# STM32.net
KiCad netlist of a schematic drawn in Altium Designer
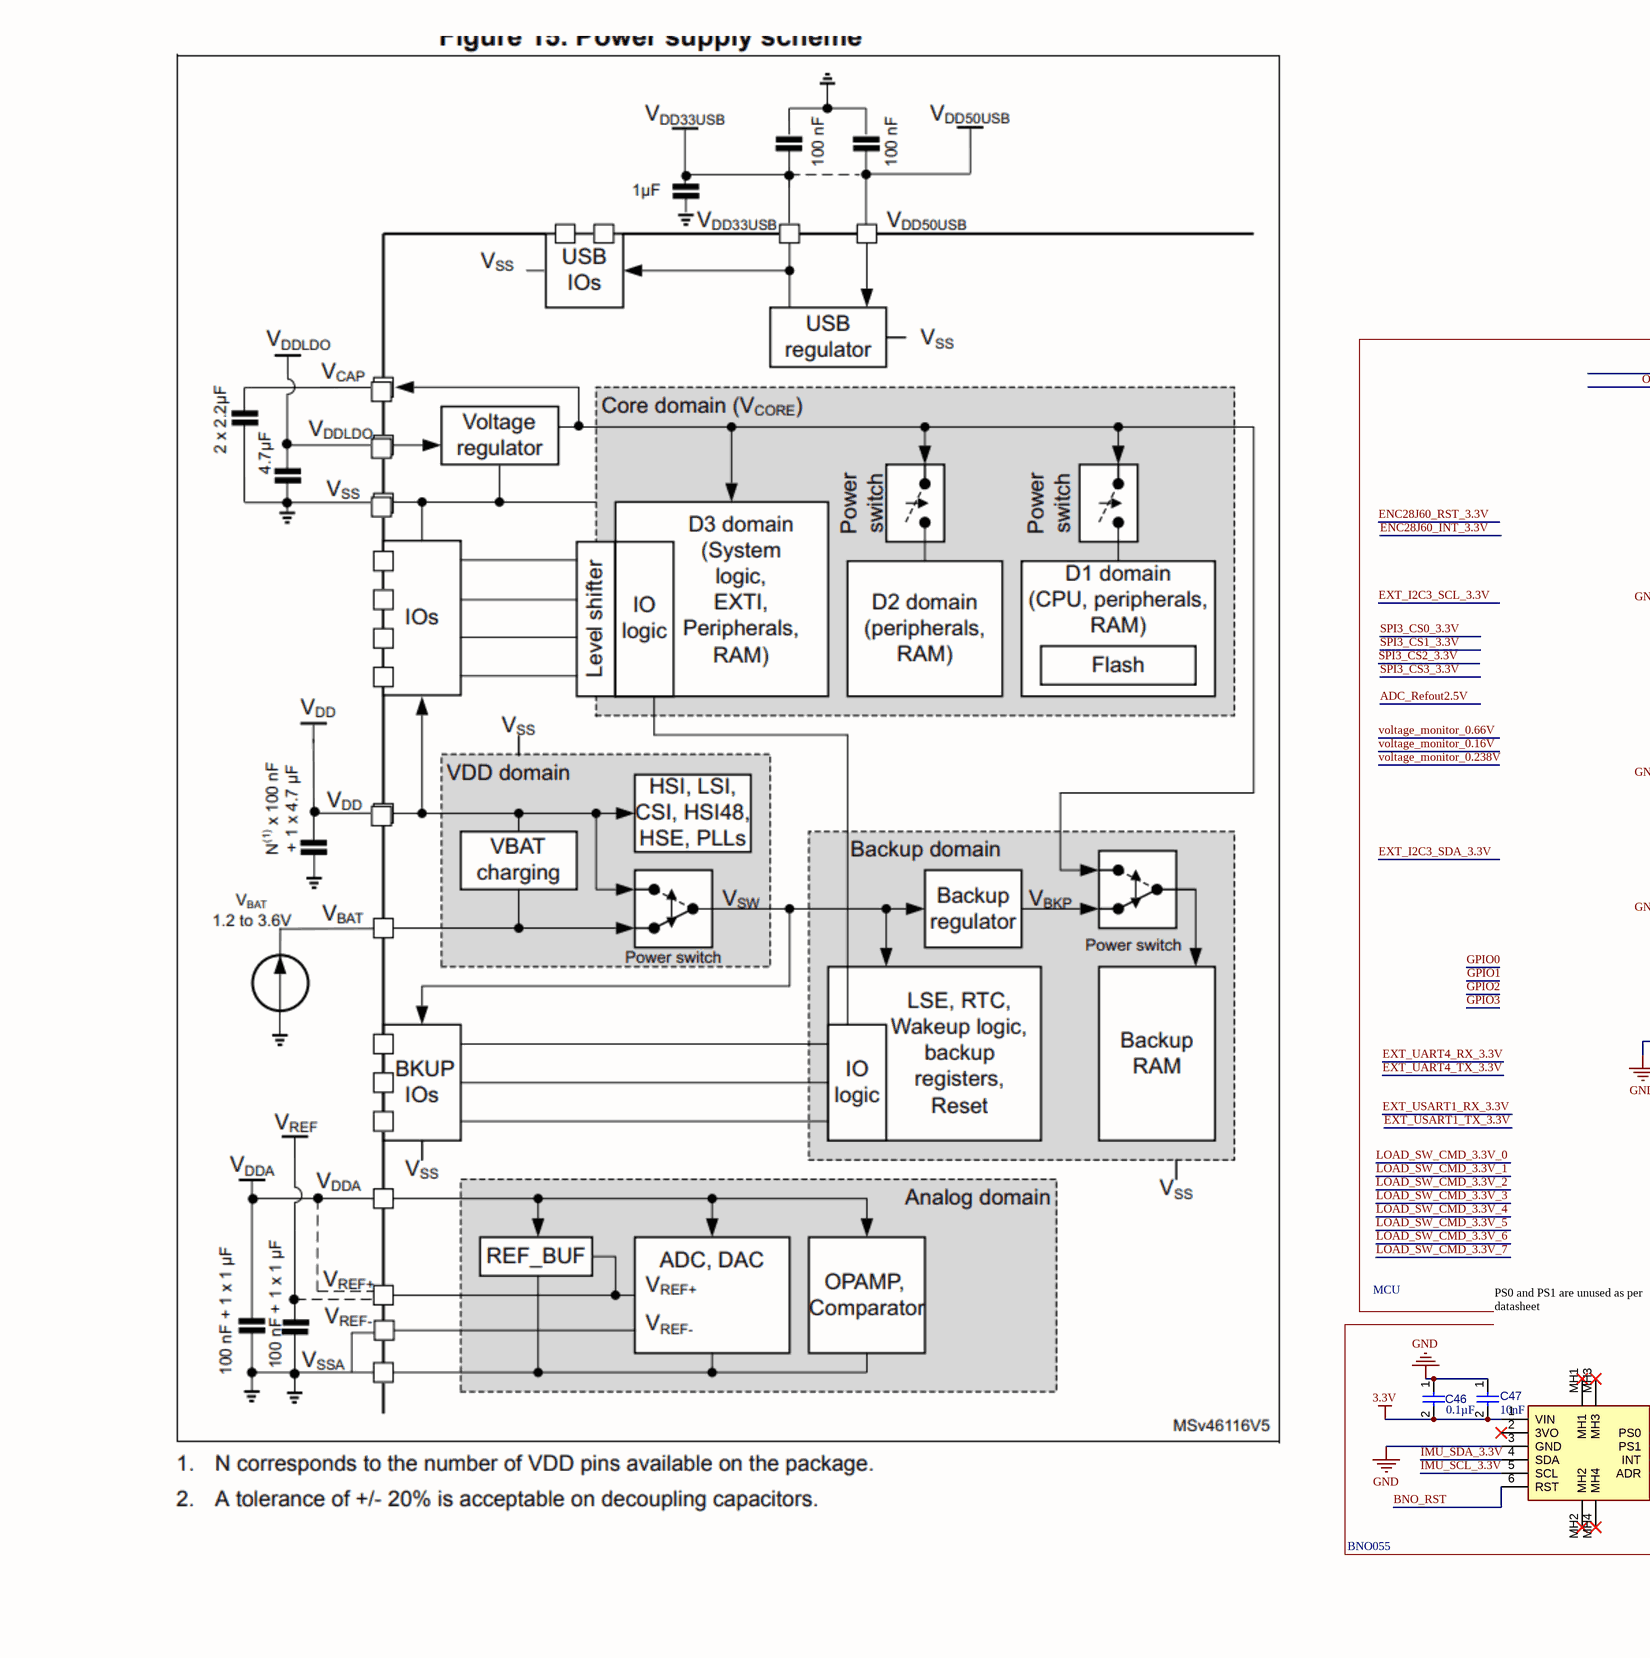
[diagram p0: STM32.SchDoc, left]
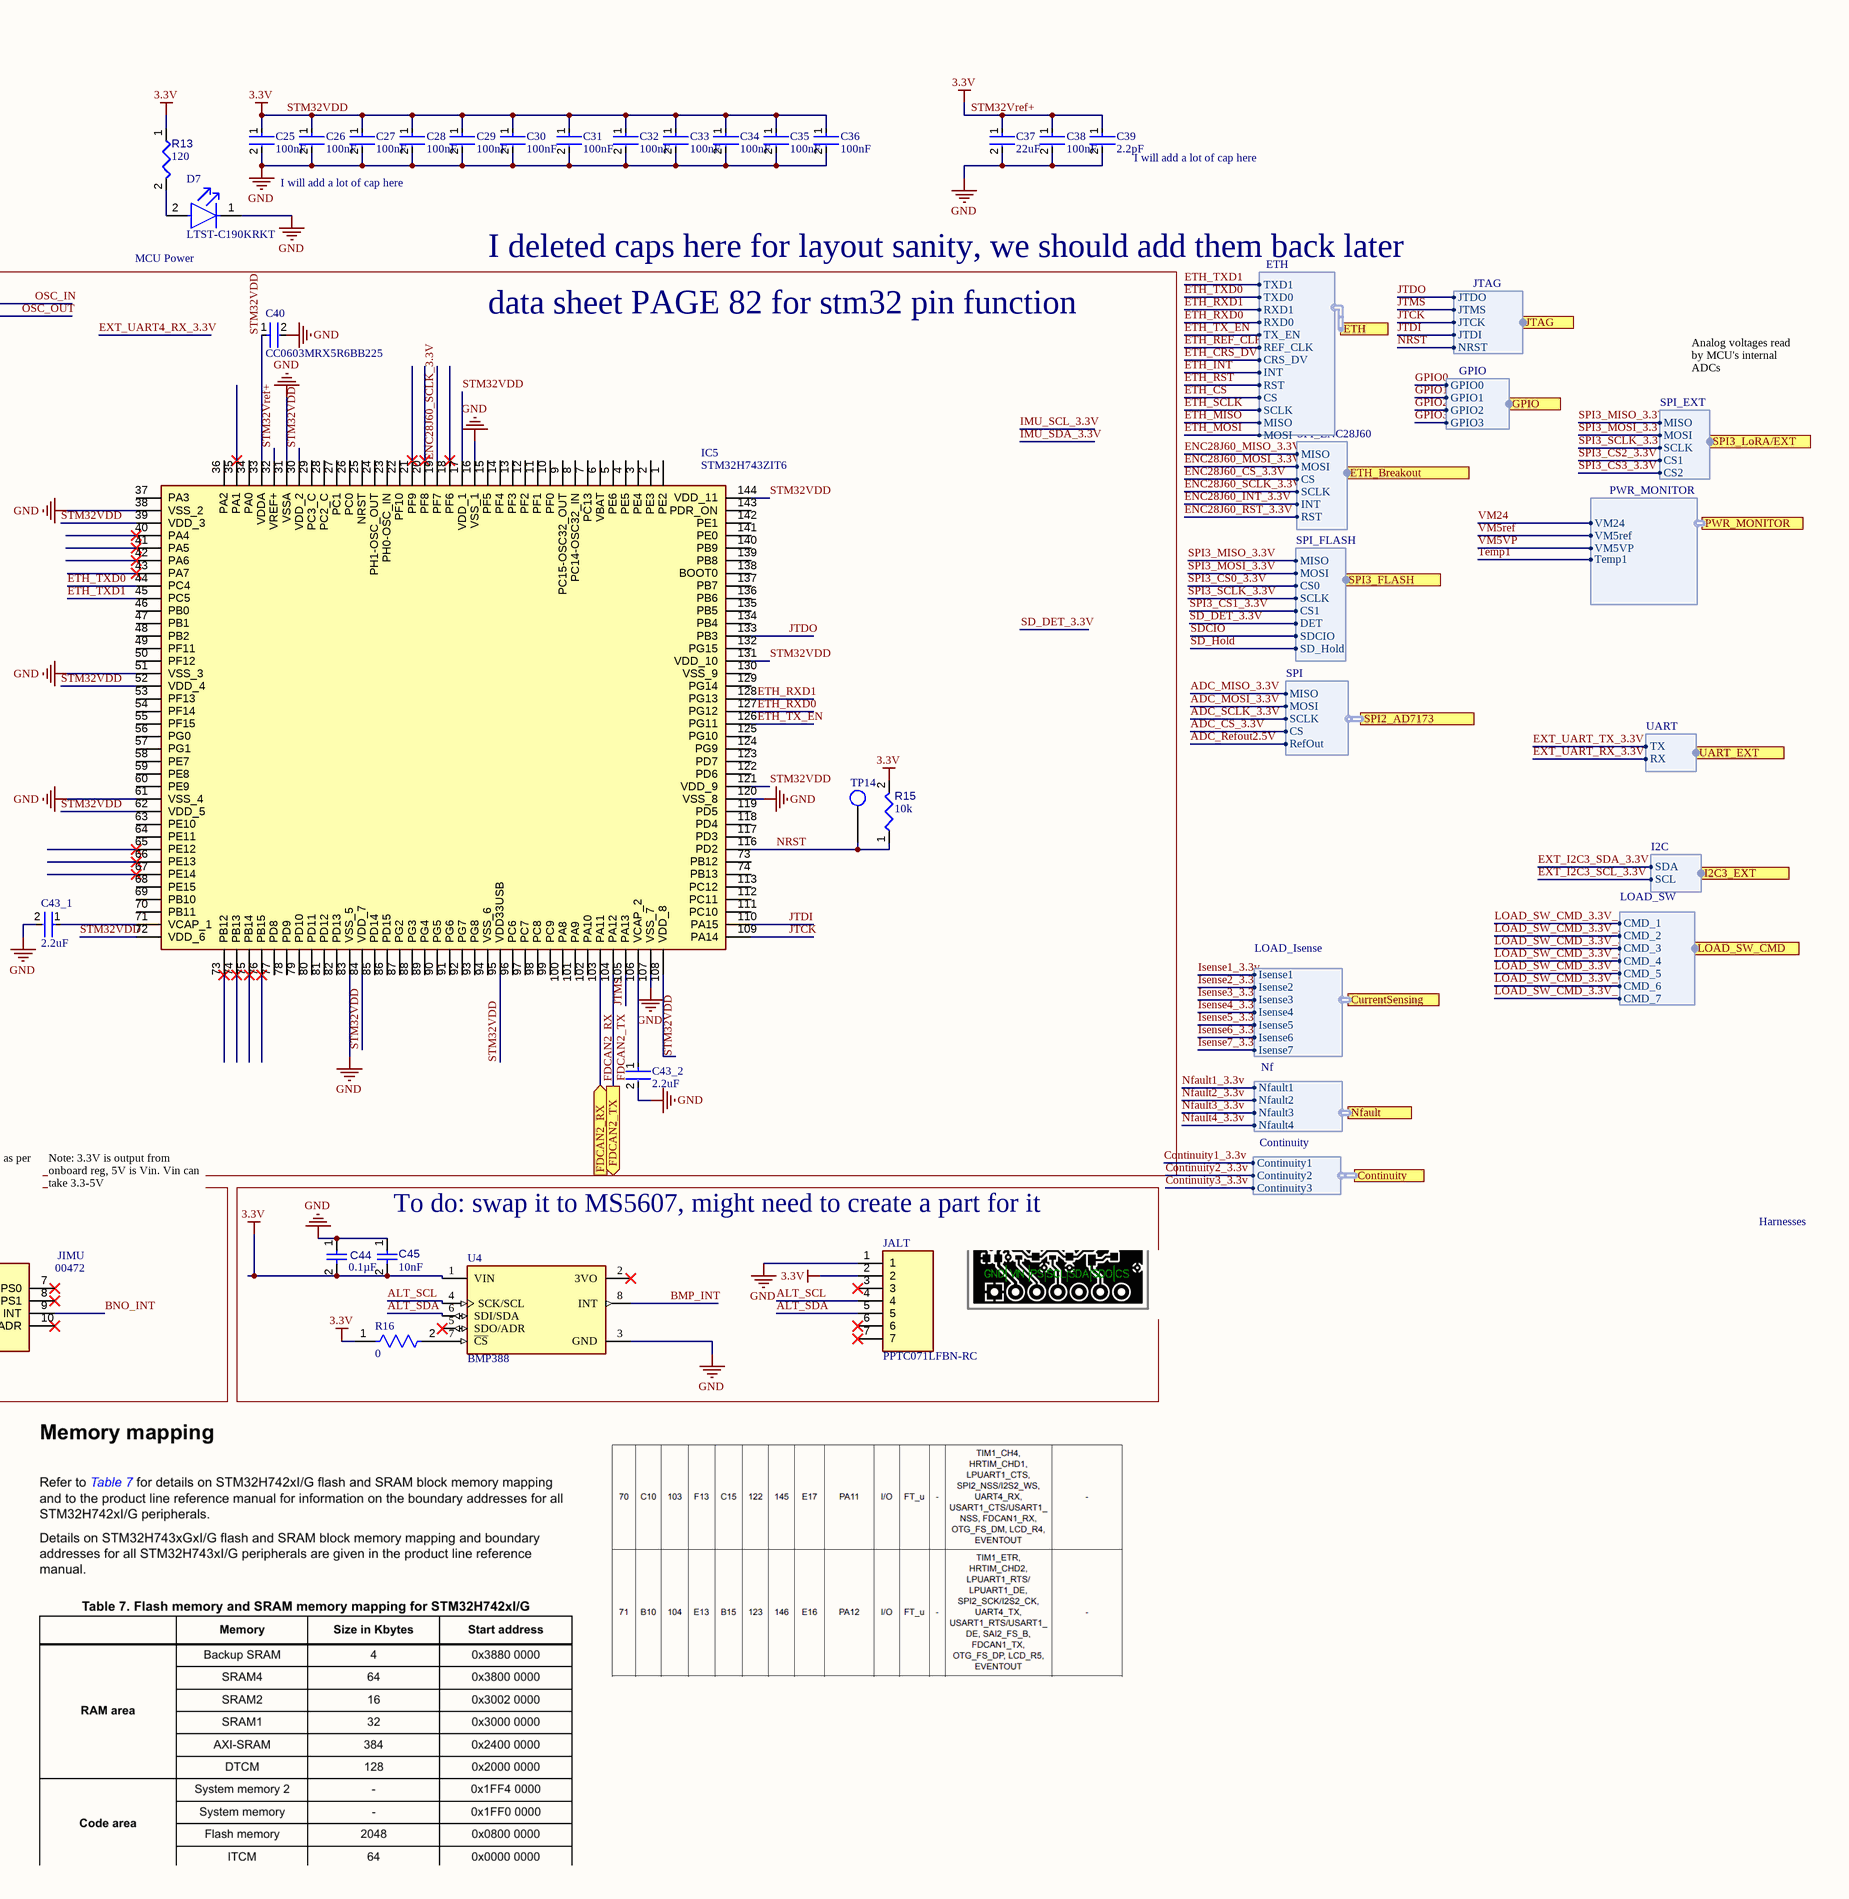
[diagram p1: STM32.SchDoc, right]

(export (version "E")
  (design (tool "Eeschema 10.0.6"))
  (components
    (comp (ref "C25")
      (value "100nF")
      (footprint "FP-CC0402-MFG")
      (description "CAP CER 0.1UF 16V X7R 0402")
      (fields (field (name "MANUFACTURER") "YAGEO") (field (name "TOLERANCE") "0.1"))
      (libsource (lib "Altium Content Vault") (part "11868f565c42a9108669ba33697ecf6"))
    )
    (comp (ref "C26")
      (value "100nF")
      (footprint "FP-CC0402-MFG")
      (description "CAP CER 0.1UF 16V X7R 0402")
      (fields (field (name "MANUFACTURER") "YAGEO") (field (name "TOLERANCE") "0.1"))
      (libsource (lib "Altium Content Vault") (part "11868f565c42a9108669ba33697ecf6"))
    )
    (comp (ref "C27")
      (value "100nF")
      (footprint "FP-CC0402-MFG")
      (description "CAP CER 0.1UF 16V X7R 0402")
      (fields (field (name "MANUFACTURER") "YAGEO") (field (name "TOLERANCE") "0.1"))
      (libsource (lib "Altium Content Vault") (part "11868f565c42a9108669ba33697ecf6"))
    )
    (comp (ref "C28")
      (value "100nF")
      (footprint "FP-CC0402-MFG")
      (description "CAP CER 0.1UF 16V X7R 0402")
      (fields (field (name "MANUFACTURER") "YAGEO") (field (name "TOLERANCE") "0.1"))
      (libsource (lib "Altium Content Vault") (part "11868f565c42a9108669ba33697ecf6"))
    )
    (comp (ref "C29")
      (value "100nF")
      (footprint "FP-CC0402-MFG")
      (description "CAP CER 0.1UF 16V X7R 0402")
      (fields (field (name "MANUFACTURER") "YAGEO") (field (name "TOLERANCE") "0.1"))
      (libsource (lib "Altium Content Vault") (part "11868f565c42a9108669ba33697ecf6"))
    )
    (comp (ref "C30")
      (value "100nF")
      (footprint "FP-CC0402-MFG")
      (description "CAP CER 0.1UF 16V X7R 0402")
      (fields (field (name "MANUFACTURER") "YAGEO") (field (name "TOLERANCE") "0.1"))
      (libsource (lib "Altium Content Vault") (part "11868f565c42a9108669ba33697ecf6"))
    )
    (comp (ref "C31")
      (value "100nF")
      (footprint "FP-CC0402-MFG")
      (description "CAP CER 0.1UF 16V X7R 0402")
      (fields (field (name "MANUFACTURER") "YAGEO") (field (name "TOLERANCE") "0.1"))
      (libsource (lib "Altium Content Vault") (part "11868f565c42a9108669ba33697ecf6"))
    )
    (comp (ref "C32")
      (value "100nF")
      (footprint "FP-CC0402-MFG")
      (description "CAP CER 0.1UF 16V X7R 0402")
      (fields (field (name "MANUFACTURER") "YAGEO") (field (name "TOLERANCE") "0.1"))
      (libsource (lib "Altium Content Vault") (part "11868f565c42a9108669ba33697ecf6"))
    )
    (comp (ref "C33")
      (value "100nF")
      (footprint "FP-CC0402-MFG")
      (description "CAP CER 0.1UF 16V X7R 0402")
      (fields (field (name "MANUFACTURER") "YAGEO") (field (name "TOLERANCE") "0.1"))
      (libsource (lib "Altium Content Vault") (part "11868f565c42a9108669ba33697ecf6"))
    )
    (comp (ref "C34")
      (value "100nF")
      (footprint "FP-CC0402-MFG")
      (description "CAP CER 0.1UF 16V X7R 0402")
      (fields (field (name "MANUFACTURER") "YAGEO") (field (name "TOLERANCE") "0.1"))
      (libsource (lib "Altium Content Vault") (part "11868f565c42a9108669ba33697ecf6"))
    )
    (comp (ref "C35")
      (value "100nF")
      (footprint "FP-CC0402-MFG")
      (description "CAP CER 0.1UF 16V X7R 0402")
      (fields (field (name "MANUFACTURER") "YAGEO") (field (name "TOLERANCE") "0.1"))
      (libsource (lib "Altium Content Vault") (part "11868f565c42a9108669ba33697ecf6"))
    )
    (comp (ref "C36")
      (value "100nF")
      (footprint "FP-CC0402-MFG")
      (description "CAP CER 0.1UF 16V X7R 0402")
      (fields (field (name "MANUFACTURER") "YAGEO") (field (name "TOLERANCE") "0.1"))
      (libsource (lib "Altium Content Vault") (part "11868f565c42a9108669ba33697ecf6"))
    )
    (comp (ref "C37")
      (value "22uF")
      (footprint "FP-CC0603-DA-MFG")
      (description "CAP CER 2.2UF 10V X5R 0603")
      (fields
        (field (name "OCTOPART") "https://octopart.com/cc0603mrx5r6bb225-yageo-40952238")
        (field (name "TOLERANCE") "0.2")
      )
      (libsource (lib "Altium Content Vault") (part "11868f565c42a9108669ba33697ecf6"))
    )
    (comp (ref "C38")
      (value "100nF")
      (footprint "FP-CGA3E-0_3-0_1-IPC_A")
      (description "Cap Ceramic 100nF 50V X7R 10% Pad SMD 0603 +125°C Automotive T/R")
      (fields (field (name "TOLERANCE") "10%") (field (name "VOLTAGE") "50V"))
      (libsource (lib "Altium Content Vault") (part "b4654b650e69147ec39a6b967a45e02"))
    )
    (comp (ref "C39")
      (value "2.2pF")
      (footprint "FP-C0603C-CF-MFG")
      (description "CAP CER 2.2PF 50V NP0 0603")
      (fields
        (field (name "MANUFACTURER PART NUMBER") "C0603C229C5GACTU")
        (field (name "MANUFACTURER") "KEMET")
      )
      (libsource (lib "Altium Content Vault") (part "b4654b650e69147ec39a6b967a45e02"))
    )
    (comp (ref "C40")
      (value "CC0603MRX5R6BB225")
      (footprint "FP-CC0603-DA-MFG")
      (description "CAP CER 2.2UF 10V X5R 0603")
      (fields
        (field (name "OCTOPART") "https://octopart.com/cc0603mrx5r6bb225-yageo-40952238")
        (field (name "TOLERANCE") "0.2")
      )
      (libsource (lib "Altium Content Vault") (part "11868f565c42a9108669ba33697ecf6"))
    )
    (comp (ref "C43_1")
      (value "2.2uF")
      (footprint "FP-CC0603-DA-MFG")
      (description "CAP CER 2.2UF 10V X5R 0603")
      (fields
        (field (name "OCTOPART") "https://octopart.com/cc0603mrx5r6bb225-yageo-40952238")
        (field (name "TOLERANCE") "0.2")
      )
      (libsource (lib "Altium Content Vault") (part "11868f565c42a9108669ba33697ecf6"))
    )
    (comp (ref "C43_2")
      (value "2.2uF")
      (footprint "FP-CC0603-DA-MFG")
      (description "CAP CER 2.2UF 10V X5R 0603")
      (fields
        (field (name "OCTOPART") "https://octopart.com/cc0603mrx5r6bb225-yageo-40952238")
        (field (name "TOLERANCE") "0.2")
      )
      (libsource (lib "Altium Content Vault") (part "11868f565c42a9108669ba33697ecf6"))
    )
    (comp (ref "C44")
      (value "0.1µF")
      (footprint "CAPC1608X90X40LL10T20")
      (description "Chip Capacitor, 1 uF, +/- 10%, 25 V, 0603 (1608 Metric)")
      (fields (field (name "TOLERANCE") "10%") (field (name "Comment") "Capacitor 1 uF +/- 10% 25 V 0603"))
      (libsource (lib "Gidon_Workspace") (part "CAP-NP-2"))
    )
    (comp (ref "C45")
      (value "10nF")
      (footprint "CAPC1608X90X40NL10T20")
      (description "Chip Capacitor, 100 nF, +/- 10%, 50 V, 0603 (1608 Metric)")
      (fields (field (name "TOLERANCE") "10%") (field (name "Comment") "Capacitor 100 nF +/-10% 50 V 0603"))
      (libsource (lib "Gidon_Workspace") (part "CAP-NP-2"))
    )
    (comp (ref "C46")
      (value "0.1µF")
      (footprint "CAPC1608X90X40LL10T20")
      (description "Chip Capacitor, 1 uF, +/- 10%, 25 V, 0603 (1608 Metric)")
      (fields (field (name "TOLERANCE") "10%") (field (name "Comment") "Capacitor 1 uF +/- 10% 25 V 0603"))
      (libsource (lib "Gidon_Workspace") (part "CAP-NP-2"))
    )
    (comp (ref "C47")
      (value "10nF")
      (footprint "CAPC1608X90X40NL10T20")
      (description "Chip Capacitor, 100 nF, +/- 10%, 50 V, 0603 (1608 Metric)")
      (fields (field (name "TOLERANCE") "10%") (field (name "Comment") "Capacitor 100 nF +/-10% 50 V 0603"))
      (libsource (lib "Gidon_Workspace") (part "CAP-NP-2"))
    )
    (comp (ref "D7")
      (value "LTST-C190KRKT")
      (footprint "FP-LTST-C190KRKT-MFG")
      (description "LED RED CLEAR CHIP SMD")
      (libsource (lib "Altium Content Vault") (part "8706943c75ba83719d021d2fdc84c58"))
    )
    (comp (ref "IC5")
      (value "STM32H743ZIT6")
      (footprint "SamacSys:QFP50P2200X2200X160-144N")
      (fields (field (name "MOUSER PART NUMBER") "511-STM32H743ZIT6"))
      (libsource (lib "*") (part "STM32H743ZIT6"))
    )
    (comp (ref "JALT")
      (value "PPTC071LFBN-RC")
      (footprint "SamacSys:RHDR7W80P0X254_1X7_1828X254X870P")
      (description "Connector")
      (libsource (lib "*") (part "PPTC071LFBN-RC"))
    )
    (comp (ref "JIMU")
      (value "00472")
      (footprint "SamacSys:00472")
      (description "Connector")
      (libsource (lib "*") (part "00472"))
    )
    (comp (ref "R13")
      (value "120")
      (footprint "RESC1609X50X30ML08T20")
      (description "Chip Resistor, 20 Ohm, +/- 1%, 100 mW, -55 to 155 degC, 0603 (1608 Metric)")
      (fields (field (name "TOLERANCE") "1%") (field (name "POWER") "100mW"))
      (libsource (lib "Charlie's Workspace") (part "RES-2"))
    )
    (comp (ref "R15")
      (value "10k")
      (footprint "RESC0402(1005)_L")
      (description "10K 0.063W 1% 0402 (1005 Metric)  SMD")
      (fields (field (name "POWER") "63mW") (field (name "TOLERANCE") "1%"))
      (libsource (lib "Yuxuan chen") (part "10KR2F"))
    )
    (comp (ref "R16")
      (value "0")
      (footprint "FP-CRCW1206-e3-MFG")
      (description "RES Thick Film, 0Ω, 0.25W, 1206")
      (libsource (lib "Altium Content Vault") (part "1029c3af85768c4190bb7ad29bc67b5"))
    )
    (comp (ref "TP14")
      (value "BURPG_TestPoint1")
      (footprint "BURPG_TestPoint1")
      (libsource (lib "BURPG_generic") (part "BURPG_TestPoint1"))
    )
    (comp (ref "U4")
      (value "BMP388")
      (footprint "FP-3966-MFG")
      (description "BMP388 - PRECISION BAROMETRIC PR")
      (libsource (lib "Altium Content Vault") (part "7ec954515874f1695838194320a9f7f"))
    )
  )
  (nets
    (net (code "20") (name "/ALT_SCL") (class "Default")
      (node (ref "JALT") (pin "4") (pinfunction "4_4") (pintype "passive"))
      (node (ref "U4") (pin "4") (pinfunction "SCK/SCL_4") (pintype "input"))
    )
    (net (code "21") (name "/ALT_SDA") (class "Default")
      (node (ref "JALT") (pin "5") (pinfunction "5_5") (pintype "passive"))
      (node (ref "U4") (pin "6") (pinfunction "SDI/SDA_6") (pintype "bidirectional"))
    )
    (net (code "22") (name "/BMP_INT") (class "Default")
      (node (ref "U4") (pin "8") (pinfunction "INT_8") (pintype "output"))
    )
    (net (code "23") (name "/BNO_INT") (class "Default")
      (node (ref "JIMU") (pin "9") (pinfunction "INT_9") (pintype "passive"))
    )
    (net (code "24") (name "/BNO_RST") (class "Default")
      (node (ref "JIMU") (pin "6") (pinfunction "RST_6") (pintype "passive"))
    )
    (net (code "33") (name "/ENC28J60_SCLK_3.3V") (class "Default")
      (node (ref "IC5") (pin "19") (pinfunction "PF7_19") (pintype "passive"))
    )
    (net (code "41") (name "/ETH_RXD0") (class "Default")
      (node (ref "IC5") (pin "127") (pinfunction "PG12_127") (pintype "passive"))
    )
    (net (code "42") (name "/ETH_RXD1") (class "Default")
      (node (ref "IC5") (pin "128") (pinfunction "PG13_128") (pintype "passive"))
    )
    (net (code "44") (name "/ETH_TXD0") (class "Default")
      (node (ref "IC5") (pin "44") (pinfunction "PC4_44") (pintype "passive"))
    )
    (net (code "45") (name "/ETH_TXD1") (class "Default")
      (node (ref "IC5") (pin "45") (pinfunction "PC5_45") (pintype "passive"))
    )
    (net (code "46") (name "/ETH_TX_EN") (class "Default")
      (node (ref "IC5") (pin "126") (pinfunction "PG11_126") (pintype "passive"))
    )
    (net (code "55") (name "/FDCAN2_RX") (class "Default")
      (node (ref "IC5") (pin "103") (pinfunction "PA11_103") (pintype "passive"))
    )
    (net (code "56") (name "/FDCAN2_TX") (class "Default")
      (node (ref "IC5") (pin "104") (pinfunction "PA12_104") (pintype "passive"))
    )
    (net (code "61") (name "/IMU_SCL_3.3V") (class "Default")
      (node (ref "JIMU") (pin "5") (pinfunction "SCL_5") (pintype "passive"))
    )
    (net (code "62") (name "/IMU_SDA_3.3V") (class "Default")
      (node (ref "JIMU") (pin "4") (pinfunction "SDA_4") (pintype "passive"))
    )
    (net (code "70") (name "/JTCK") (class "Default")
      (node (ref "IC5") (pin "109") (pinfunction "PA14_109") (pintype "passive"))
    )
    (net (code "71") (name "/JTDI") (class "Default")
      (node (ref "IC5") (pin "110") (pinfunction "PA15_110") (pintype "passive"))
    )
    (net (code "72") (name "/JTDO") (class "Default")
      (node (ref "IC5") (pin "133") (pinfunction "PB3_133") (pintype "passive"))
    )
    (net (code "73") (name "/JTMS") (class "Default")
      (node (ref "IC5") (pin "105") (pinfunction "PA13_105") (pintype "passive"))
    )
    (net (code "82") (name "/NRST") (class "Default")
      (node (ref "IC5") (pin "116") (pinfunction "PD2_116") (pintype "passive"))
      (node (ref "R15") (pin "1") (pinfunction "1_1") (pintype "passive"))
      (node (ref "TP14") (pin "1") (pinfunction "1_1") (pintype "passive"))
    )
    (net (code "120") (name "3.3V") (class "Default")
      (node (ref "C25") (pin "1") (pinfunction "1_1") (pintype "passive"))
      (node (ref "C26") (pin "1") (pinfunction "1_1") (pintype "passive"))
      (node (ref "C27") (pin "1") (pinfunction "1_1") (pintype "passive"))
      (node (ref "C28") (pin "1") (pinfunction "1_1") (pintype "passive"))
      (node (ref "C29") (pin "1") (pinfunction "1_1") (pintype "passive"))
      (node (ref "C30") (pin "1") (pinfunction "1_1") (pintype "passive"))
      (node (ref "C31") (pin "1") (pinfunction "1_1") (pintype "passive"))
      (node (ref "C32") (pin "1") (pinfunction "1_1") (pintype "passive"))
      (node (ref "C33") (pin "1") (pinfunction "1_1") (pintype "passive"))
      (node (ref "C34") (pin "1") (pinfunction "1_1") (pintype "passive"))
      (node (ref "C35") (pin "1") (pinfunction "1_1") (pintype "passive"))
      (node (ref "C36") (pin "1") (pinfunction "1_1") (pintype "passive"))
      (node (ref "C37") (pin "1") (pinfunction "1_1") (pintype "passive"))
      (node (ref "C38") (pin "1") (pinfunction "1_1") (pintype "passive"))
      (node (ref "C39") (pin "1") (pinfunction "1_1") (pintype "passive"))
      (node (ref "C40") (pin "1") (pinfunction "1_1") (pintype "passive"))
      (node (ref "C44") (pin "2") (pinfunction "2_2") (pintype "passive"))
      (node (ref "C45") (pin "2") (pinfunction "2_2") (pintype "passive"))
      (node (ref "C46") (pin "2") (pinfunction "2_2") (pintype "passive"))
      (node (ref "C47") (pin "2") (pinfunction "2_2") (pintype "passive"))
      (node (ref "IC5") (pin "108") (pinfunction "VDD_8_108") (pintype "passive"))
      (node (ref "IC5") (pin "121") (pinfunction "VDD_9_121") (pintype "passive"))
      (node (ref "IC5") (pin "131") (pinfunction "VDD_10_131") (pintype "passive"))
      (node (ref "IC5") (pin "144") (pinfunction "VDD_11_144") (pintype "passive"))
      (node (ref "IC5") (pin "17") (pinfunction "VDD_1_17") (pintype "passive"))
      (node (ref "IC5") (pin "30") (pinfunction "VDD_2_30") (pintype "passive"))
      (node (ref "IC5") (pin "32") (pinfunction "VREF+_32") (pintype "passive"))
      (node (ref "IC5") (pin "33") (pinfunction "VDDA_33") (pintype "passive"))
      (node (ref "IC5") (pin "39") (pinfunction "VDD_3_39") (pintype "passive"))
      (node (ref "IC5") (pin "52") (pinfunction "VDD_4_52") (pintype "passive"))
      (node (ref "IC5") (pin "62") (pinfunction "VDD_5_62") (pintype "passive"))
      (node (ref "IC5") (pin "72") (pinfunction "VDD_6_72") (pintype "passive"))
      (node (ref "IC5") (pin "84") (pinfunction "VDD_7_84") (pintype "passive"))
      (node (ref "IC5") (pin "95") (pinfunction "VDD33USB_95") (pintype "passive"))
      (node (ref "JALT") (pin "2") (pinfunction "2_2") (pintype "passive"))
      (node (ref "JIMU") (pin "1") (pinfunction "VIN_1") (pintype "passive"))
      (node (ref "R13") (pin "1") (pinfunction "1_1") (pintype "passive"))
      (node (ref "R15") (pin "2") (pinfunction "2_2") (pintype "passive"))
      (node (ref "R16") (pin "1") (pinfunction "1_1") (pintype "passive"))
      (node (ref "U4") (pin "1") (pinfunction "VIN_1") (pintype "power_in"))
    )
    (net (code "121") (name "GND") (class "Default")
      (node (ref "C25") (pin "2") (pinfunction "2_2") (pintype "passive"))
      (node (ref "C26") (pin "2") (pinfunction "2_2") (pintype "passive"))
      (node (ref "C27") (pin "2") (pinfunction "2_2") (pintype "passive"))
      (node (ref "C28") (pin "2") (pinfunction "2_2") (pintype "passive"))
      (node (ref "C29") (pin "2") (pinfunction "2_2") (pintype "passive"))
      (node (ref "C30") (pin "2") (pinfunction "2_2") (pintype "passive"))
      (node (ref "C31") (pin "2") (pinfunction "2_2") (pintype "passive"))
      (node (ref "C32") (pin "2") (pinfunction "2_2") (pintype "passive"))
      (node (ref "C33") (pin "2") (pinfunction "2_2") (pintype "passive"))
      (node (ref "C34") (pin "2") (pinfunction "2_2") (pintype "passive"))
      (node (ref "C35") (pin "2") (pinfunction "2_2") (pintype "passive"))
      (node (ref "C36") (pin "2") (pinfunction "2_2") (pintype "passive"))
      (node (ref "C37") (pin "2") (pinfunction "2_2") (pintype "passive"))
      (node (ref "C38") (pin "2") (pinfunction "2_2") (pintype "passive"))
      (node (ref "C39") (pin "2") (pinfunction "2_2") (pintype "passive"))
      (node (ref "C40") (pin "2") (pinfunction "2_2") (pintype "passive"))
      (node (ref "C43_1") (pin "2") (pinfunction "2_2") (pintype "passive"))
      (node (ref "C43_2") (pin "2") (pinfunction "2_2") (pintype "passive"))
      (node (ref "C44") (pin "1") (pinfunction "1_1") (pintype "passive"))
      (node (ref "C45") (pin "1") (pinfunction "1_1") (pintype "passive"))
      (node (ref "C46") (pin "1") (pinfunction "1_1") (pintype "passive"))
      (node (ref "C47") (pin "1") (pinfunction "1_1") (pintype "passive"))
      (node (ref "D7") (pin "1") (pinfunction "C_1") (pintype "passive"))
      (node (ref "IC5") (pin "107") (pinfunction "VSS_7_107") (pintype "passive"))
      (node (ref "IC5") (pin "120") (pinfunction "VSS_8_120") (pintype "passive"))
      (node (ref "IC5") (pin "16") (pinfunction "VSS_1_16") (pintype "passive"))
      (node (ref "IC5") (pin "31") (pinfunction "VSSA_31") (pintype "passive"))
      (node (ref "IC5") (pin "38") (pinfunction "VSS_2_38") (pintype "passive"))
      (node (ref "IC5") (pin "51") (pinfunction "VSS_3_51") (pintype "passive"))
      (node (ref "IC5") (pin "61") (pinfunction "VSS_4_61") (pintype "passive"))
      (node (ref "IC5") (pin "83") (pinfunction "VSS_5_83") (pintype "passive"))
      (node (ref "JALT") (pin "1") (pinfunction "1_1") (pintype "passive"))
      (node (ref "JIMU") (pin "3") (pinfunction "GND_3") (pintype "passive"))
      (node (ref "U4") (pin "3") (pinfunction "GND_3") (pintype "power_in"))
    )
    (net (code "122") (name "Net-(D7-A)") (class "Default")
      (node (ref "D7") (pin "2") (pinfunction "A_2") (pintype "passive"))
      (node (ref "R13") (pin "2") (pinfunction "2_2") (pintype "passive"))
    )
    (net (code "123") (name "Net-(IC5-VCAP_1)") (class "Default")
      (node (ref "C43_1") (pin "1") (pinfunction "1_1") (pintype "passive"))
      (node (ref "IC5") (pin "71") (pinfunction "VCAP_1_71") (pintype "passive"))
    )
    (net (code "124") (name "Net-(IC5-VCAP_2)") (class "Default")
      (node (ref "C43_2") (pin "1") (pinfunction "1_1") (pintype "passive"))
      (node (ref "IC5") (pin "106") (pinfunction "VCAP_2_106") (pintype "passive"))
    )
    (net (code "125") (name "Net-(U4-~{CS})") (class "Default")
      (node (ref "R16") (pin "2") (pinfunction "2_2") (pintype "passive"))
      (node (ref "U4") (pin "7") (pinfunction "~{CS}_7") (pintype "input"))
    )
    (net (code "126") (name "unconnected-(IC5-BOOT0-Pad138)") (class "Default")
      (node (ref "IC5") (pin "138") (pinfunction "BOOT0_138") (pintype "passive"))
    )
    (net (code "127") (name "unconnected-(IC5-NRST-Pad25)") (class "Default")
      (node (ref "IC5") (pin "25") (pinfunction "NRST_25") (pintype "passive"))
    )
    (net (code "128") (name "unconnected-(IC5-PA0-Pad34)") (class "Default")
      (node (ref "IC5") (pin "34") (pinfunction "PA0_34") (pintype "passive"))
    )
    (net (code "129") (name "unconnected-(IC5-PA1-Pad35)") (class "Default")
      (node (ref "IC5") (pin "35") (pinfunction "PA1_35") (pintype "passive+no_connect"))
    )
    (net (code "130") (name "unconnected-(IC5-PA2-Pad36)") (class "Default")
      (node (ref "IC5") (pin "36") (pinfunction "PA2_36") (pintype "passive"))
    )
    (net (code "131") (name "unconnected-(IC5-PA3-Pad37)") (class "Default")
      (node (ref "IC5") (pin "37") (pinfunction "PA3_37") (pintype "passive"))
    )
    (net (code "132") (name "unconnected-(IC5-PA4-Pad40)") (class "Default")
      (node (ref "IC5") (pin "40") (pinfunction "PA4_40") (pintype "passive+no_connect"))
    )
    (net (code "133") (name "unconnected-(IC5-PA5-Pad41)") (class "Default")
      (node (ref "IC5") (pin "41") (pinfunction "PA5_41") (pintype "passive+no_connect"))
    )
    (net (code "134") (name "unconnected-(IC5-PA6-Pad42)") (class "Default")
      (node (ref "IC5") (pin "42") (pinfunction "PA6_42") (pintype "passive+no_connect"))
    )
    (net (code "135") (name "unconnected-(IC5-PA7-Pad43)") (class "Default")
      (node (ref "IC5") (pin "43") (pinfunction "PA7_43") (pintype "passive+no_connect"))
    )
    (net (code "136") (name "unconnected-(IC5-PA8-Pad100)") (class "Default")
      (node (ref "IC5") (pin "100") (pinfunction "PA8_100") (pintype "passive"))
    )
    (net (code "137") (name "unconnected-(IC5-PA9-Pad101)") (class "Default")
      (node (ref "IC5") (pin "101") (pinfunction "PA9_101") (pintype "passive"))
    )
    (net (code "138") (name "unconnected-(IC5-PA10-Pad102)") (class "Default")
      (node (ref "IC5") (pin "102") (pinfunction "PA10_102") (pintype "passive"))
    )
    (net (code "139") (name "unconnected-(IC5-PB0-Pad46)") (class "Default")
      (node (ref "IC5") (pin "46") (pinfunction "PB0_46") (pintype "passive"))
    )
    (net (code "140") (name "unconnected-(IC5-PB1-Pad47)") (class "Default")
      (node (ref "IC5") (pin "47") (pinfunction "PB1_47") (pintype "passive"))
    )
    (net (code "141") (name "unconnected-(IC5-PB2-Pad48)") (class "Default")
      (node (ref "IC5") (pin "48") (pinfunction "PB2_48") (pintype "passive"))
    )
    (net (code "142") (name "unconnected-(IC5-PB4-Pad134)") (class "Default")
      (node (ref "IC5") (pin "134") (pinfunction "PB4_134") (pintype "passive"))
    )
    (net (code "143") (name "unconnected-(IC5-PB5-Pad135)") (class "Default")
      (node (ref "IC5") (pin "135") (pinfunction "PB5_135") (pintype "passive"))
    )
    (net (code "144") (name "unconnected-(IC5-PB6-Pad136)") (class "Default")
      (node (ref "IC5") (pin "136") (pinfunction "PB6_136") (pintype "passive"))
    )
    (net (code "145") (name "unconnected-(IC5-PB7-Pad137)") (class "Default")
      (node (ref "IC5") (pin "137") (pinfunction "PB7_137") (pintype "passive"))
    )
    (net (code "146") (name "unconnected-(IC5-PB8-Pad139)") (class "Default")
      (node (ref "IC5") (pin "139") (pinfunction "PB8_139") (pintype "passive"))
    )
    (net (code "147") (name "unconnected-(IC5-PB9-Pad140)") (class "Default")
      (node (ref "IC5") (pin "140") (pinfunction "PB9_140") (pintype "passive"))
    )
    (net (code "148") (name "unconnected-(IC5-PB10-Pad69)") (class "Default")
      (node (ref "IC5") (pin "69") (pinfunction "PB10_69") (pintype "passive"))
    )
    (net (code "149") (name "unconnected-(IC5-PB11-Pad70)") (class "Default")
      (node (ref "IC5") (pin "70") (pinfunction "PB11_70") (pintype "passive"))
    )
    (net (code "150") (name "unconnected-(IC5-PB12-Pad73)") (class "Default")
      (node (ref "IC5") (pin "73") (pinfunction "PB12_73") (pintype "passive"))
    )
    (net (code "151") (name "unconnected-(IC5-PB12-Pad73)") (class "Default")
      (node (ref "IC5") (pin "73") (pinfunction "PB12_73") (pintype "passive+no_connect"))
    )
    (net (code "152") (name "unconnected-(IC5-PB13-Pad74)") (class "Default")
      (node (ref "IC5") (pin "74") (pinfunction "PB13_74") (pintype "passive+no_connect"))
    )
    (net (code "153") (name "unconnected-(IC5-PB13-Pad74)") (class "Default")
      (node (ref "IC5") (pin "74") (pinfunction "PB13_74") (pintype "passive"))
    )
    (net (code "154") (name "unconnected-(IC5-PB14-Pad75)") (class "Default")
      (node (ref "IC5") (pin "75") (pinfunction "PB14_75") (pintype "passive+no_connect"))
    )
    (net (code "155") (name "unconnected-(IC5-PB15-Pad76)") (class "Default")
      (node (ref "IC5") (pin "76") (pinfunction "PB15_76") (pintype "passive+no_connect"))
    )
    (net (code "156") (name "unconnected-(IC5-PC0-Pad26)") (class "Default")
      (node (ref "IC5") (pin "26") (pinfunction "PC0_26") (pintype "passive"))
    )
    (net (code "157") (name "unconnected-(IC5-PC1-Pad27)") (class "Default")
      (node (ref "IC5") (pin "27") (pinfunction "PC1_27") (pintype "passive"))
    )
    (net (code "158") (name "unconnected-(IC5-PC2_C-Pad28)") (class "Default")
      (node (ref "IC5") (pin "28") (pinfunction "PC2_C_28") (pintype "passive"))
    )
    (net (code "159") (name "unconnected-(IC5-PC3_C-Pad29)") (class "Default")
      (node (ref "IC5") (pin "29") (pinfunction "PC3_C_29") (pintype "passive"))
    )
    (net (code "160") (name "unconnected-(IC5-PC6-Pad96)") (class "Default")
      (node (ref "IC5") (pin "96") (pinfunction "PC6_96") (pintype "passive"))
    )
    (net (code "161") (name "unconnected-(IC5-PC7-Pad97)") (class "Default")
      (node (ref "IC5") (pin "97") (pinfunction "PC7_97") (pintype "passive"))
    )
    (net (code "162") (name "unconnected-(IC5-PC8-Pad98)") (class "Default")
      (node (ref "IC5") (pin "98") (pinfunction "PC8_98") (pintype "passive"))
    )
    (net (code "163") (name "unconnected-(IC5-PC9-Pad99)") (class "Default")
      (node (ref "IC5") (pin "99") (pinfunction "PC9_99") (pintype "passive"))
    )
    (net (code "164") (name "unconnected-(IC5-PC10-Pad111)") (class "Default")
      (node (ref "IC5") (pin "111") (pinfunction "PC10_111") (pintype "passive"))
    )
    (net (code "165") (name "unconnected-(IC5-PC11-Pad112)") (class "Default")
      (node (ref "IC5") (pin "112") (pinfunction "PC11_112") (pintype "passive"))
    )
    (net (code "166") (name "unconnected-(IC5-PC12-Pad113)") (class "Default")
      (node (ref "IC5") (pin "113") (pinfunction "PC12_113") (pintype "passive"))
    )
    (net (code "167") (name "unconnected-(IC5-PC13-Pad7)") (class "Default")
      (node (ref "IC5") (pin "7") (pinfunction "PC13_7") (pintype "passive"))
    )
    (net (code "168") (name "unconnected-(IC5-PC14-OSC32_IN-Pad8)") (class "Default")
      (node (ref "IC5") (pin "8") (pinfunction "PC14-OSC32_IN_8") (pintype "passive"))
    )
    (net (code "169") (name "unconnected-(IC5-PC15-OSC32_OUT-Pad9)") (class "Default")
      (node (ref "IC5") (pin "9") (pinfunction "PC15-OSC32_OUT_9") (pintype "passive"))
    )
    (net (code "170") (name "unconnected-(IC5-PD3-Pad117)") (class "Default")
      (node (ref "IC5") (pin "117") (pinfunction "PD3_117") (pintype "passive"))
    )
    (net (code "171") (name "unconnected-(IC5-PD4-Pad118)") (class "Default")
      (node (ref "IC5") (pin "118") (pinfunction "PD4_118") (pintype "passive"))
    )
    (net (code "172") (name "unconnected-(IC5-PD5-Pad119)") (class "Default")
      (node (ref "IC5") (pin "119") (pinfunction "PD5_119") (pintype "passive"))
    )
    (net (code "173") (name "unconnected-(IC5-PD6-Pad122)") (class "Default")
      (node (ref "IC5") (pin "122") (pinfunction "PD6_122") (pintype "passive"))
    )
    (net (code "174") (name "unconnected-(IC5-PD7-Pad123)") (class "Default")
      (node (ref "IC5") (pin "123") (pinfunction "PD7_123") (pintype "passive"))
    )
    (net (code "175") (name "unconnected-(IC5-PD8-Pad77)") (class "Default")
      (node (ref "IC5") (pin "77") (pinfunction "PD8_77") (pintype "passive"))
    )
    (net (code "176") (name "unconnected-(IC5-PD9-Pad78)") (class "Default")
      (node (ref "IC5") (pin "78") (pinfunction "PD9_78") (pintype "passive"))
    )
    (net (code "177") (name "unconnected-(IC5-PD10-Pad79)") (class "Default")
      (node (ref "IC5") (pin "79") (pinfunction "PD10_79") (pintype "passive"))
    )
    (net (code "178") (name "unconnected-(IC5-PD11-Pad80)") (class "Default")
      (node (ref "IC5") (pin "80") (pinfunction "PD11_80") (pintype "passive"))
    )
    (net (code "179") (name "unconnected-(IC5-PD12-Pad81)") (class "Default")
      (node (ref "IC5") (pin "81") (pinfunction "PD12_81") (pintype "passive"))
    )
    (net (code "180") (name "unconnected-(IC5-PD13-Pad82)") (class "Default")
      (node (ref "IC5") (pin "82") (pinfunction "PD13_82") (pintype "passive"))
    )
    (net (code "181") (name "unconnected-(IC5-PD14-Pad85)") (class "Default")
      (node (ref "IC5") (pin "85") (pinfunction "PD14_85") (pintype "passive"))
    )
    (net (code "182") (name "unconnected-(IC5-PD15-Pad86)") (class "Default")
      (node (ref "IC5") (pin "86") (pinfunction "PD15_86") (pintype "passive"))
    )
    (net (code "183") (name "unconnected-(IC5-PDR_ON-Pad143)") (class "Default")
      (node (ref "IC5") (pin "143") (pinfunction "PDR_ON_143") (pintype "passive"))
    )
    (net (code "184") (name "unconnected-(IC5-PE0-Pad141)") (class "Default")
      (node (ref "IC5") (pin "141") (pinfunction "PE0_141") (pintype "passive"))
    )
    (net (code "185") (name "unconnected-(IC5-PE1-Pad142)") (class "Default")
      (node (ref "IC5") (pin "142") (pinfunction "PE1_142") (pintype "passive"))
    )
    (net (code "186") (name "unconnected-(IC5-PE2-Pad1)") (class "Default")
      (node (ref "IC5") (pin "1") (pinfunction "PE2_1") (pintype "power_in"))
    )
    (net (code "187") (name "unconnected-(IC5-PE3-Pad2)") (class "Default")
      (node (ref "IC5") (pin "2") (pinfunction "PE3_2") (pintype "passive"))
    )
    (net (code "188") (name "unconnected-(IC5-PE4-Pad3)") (class "Default")
      (node (ref "IC5") (pin "3") (pinfunction "PE4_3") (pintype "passive"))
    )
    (net (code "189") (name "unconnected-(IC5-PE5-Pad4)") (class "Default")
      (node (ref "IC5") (pin "4") (pinfunction "PE5_4") (pintype "passive"))
    )
    (net (code "190") (name "unconnected-(IC5-PE6-Pad5)") (class "Default")
      (node (ref "IC5") (pin "5") (pinfunction "PE6_5") (pintype "passive"))
    )
    (net (code "191") (name "unconnected-(IC5-PE7-Pad58)") (class "Default")
      (node (ref "IC5") (pin "58") (pinfunction "PE7_58") (pintype "passive"))
    )
    (net (code "192") (name "unconnected-(IC5-PE8-Pad59)") (class "Default")
      (node (ref "IC5") (pin "59") (pinfunction "PE8_59") (pintype "passive"))
    )
    (net (code "193") (name "unconnected-(IC5-PE9-Pad60)") (class "Default")
      (node (ref "IC5") (pin "60") (pinfunction "PE9_60") (pintype "passive"))
    )
    (net (code "194") (name "unconnected-(IC5-PE10-Pad63)") (class "Default")
      (node (ref "IC5") (pin "63") (pinfunction "PE10_63") (pintype "passive"))
    )
    (net (code "195") (name "unconnected-(IC5-PE11-Pad64)") (class "Default")
      (node (ref "IC5") (pin "64") (pinfunction "PE11_64") (pintype "passive"))
    )
    (net (code "196") (name "unconnected-(IC5-PE12-Pad65)") (class "Default")
      (node (ref "IC5") (pin "65") (pinfunction "PE12_65") (pintype "passive+no_connect"))
    )
    (net (code "197") (name "unconnected-(IC5-PE13-Pad66)") (class "Default")
      (node (ref "IC5") (pin "66") (pinfunction "PE13_66") (pintype "passive+no_connect"))
    )
    (net (code "198") (name "unconnected-(IC5-PE14-Pad67)") (class "Default")
      (node (ref "IC5") (pin "67") (pinfunction "PE14_67") (pintype "passive+no_connect"))
    )
    (net (code "199") (name "unconnected-(IC5-PE15-Pad68)") (class "Default")
      (node (ref "IC5") (pin "68") (pinfunction "PE15_68") (pintype "passive"))
    )
    (net (code "200") (name "unconnected-(IC5-PF0-Pad10)") (class "Default")
      (node (ref "IC5") (pin "10") (pinfunction "PF0_10") (pintype "passive"))
    )
    (net (code "201") (name "unconnected-(IC5-PF1-Pad11)") (class "Default")
      (node (ref "IC5") (pin "11") (pinfunction "PF1_11") (pintype "passive"))
    )
    (net (code "202") (name "unconnected-(IC5-PF2-Pad12)") (class "Default")
      (node (ref "IC5") (pin "12") (pinfunction "PF2_12") (pintype "passive"))
    )
    (net (code "203") (name "unconnected-(IC5-PF3-Pad13)") (class "Default")
      (node (ref "IC5") (pin "13") (pinfunction "PF3_13") (pintype "passive"))
    )
    (net (code "204") (name "unconnected-(IC5-PF4-Pad14)") (class "Default")
      (node (ref "IC5") (pin "14") (pinfunction "PF4_14") (pintype "passive"))
    )
    (net (code "205") (name "unconnected-(IC5-PF5-Pad15)") (class "Default")
      (node (ref "IC5") (pin "15") (pinfunction "PF5_15") (pintype "passive"))
    )
    (net (code "206") (name "unconnected-(IC5-PF6-Pad18)") (class "Default")
      (node (ref "IC5") (pin "18") (pinfunction "PF6_18") (pintype "passive+no_connect"))
    )
    (net (code "207") (name "unconnected-(IC5-PF8-Pad20)") (class "Default")
      (node (ref "IC5") (pin "20") (pinfunction "PF8_20") (pintype "passive+no_connect"))
    )
    (net (code "208") (name "unconnected-(IC5-PF9-Pad21)") (class "Default")
      (node (ref "IC5") (pin "21") (pinfunction "PF9_21") (pintype "passive+no_connect"))
    )
    (net (code "209") (name "unconnected-(IC5-PF10-Pad22)") (class "Default")
      (node (ref "IC5") (pin "22") (pinfunction "PF10_22") (pintype "passive"))
    )
    (net (code "210") (name "unconnected-(IC5-PF11-Pad49)") (class "Default")
      (node (ref "IC5") (pin "49") (pinfunction "PF11_49") (pintype "passive"))
    )
    (net (code "211") (name "unconnected-(IC5-PF12-Pad50)") (class "Default")
      (node (ref "IC5") (pin "50") (pinfunction "PF12_50") (pintype "passive"))
    )
    (net (code "212") (name "unconnected-(IC5-PF13-Pad53)") (class "Default")
      (node (ref "IC5") (pin "53") (pinfunction "PF13_53") (pintype "passive"))
    )
    (net (code "213") (name "unconnected-(IC5-PF14-Pad54)") (class "Default")
      (node (ref "IC5") (pin "54") (pinfunction "PF14_54") (pintype "passive"))
    )
    (net (code "214") (name "unconnected-(IC5-PF15-Pad55)") (class "Default")
      (node (ref "IC5") (pin "55") (pinfunction "PF15_55") (pintype "passive"))
    )
    (net (code "215") (name "unconnected-(IC5-PG0-Pad56)") (class "Default")
      (node (ref "IC5") (pin "56") (pinfunction "PG0_56") (pintype "passive"))
    )
    (net (code "216") (name "unconnected-(IC5-PG1-Pad57)") (class "Default")
      (node (ref "IC5") (pin "57") (pinfunction "PG1_57") (pintype "passive"))
    )
    (net (code "217") (name "unconnected-(IC5-PG2-Pad87)") (class "Default")
      (node (ref "IC5") (pin "87") (pinfunction "PG2_87") (pintype "passive"))
    )
    (net (code "218") (name "unconnected-(IC5-PG3-Pad88)") (class "Default")
      (node (ref "IC5") (pin "88") (pinfunction "PG3_88") (pintype "passive"))
    )
    (net (code "219") (name "unconnected-(IC5-PG4-Pad89)") (class "Default")
      (node (ref "IC5") (pin "89") (pinfunction "PG4_89") (pintype "passive"))
    )
    (net (code "220") (name "unconnected-(IC5-PG5-Pad90)") (class "Default")
      (node (ref "IC5") (pin "90") (pinfunction "PG5_90") (pintype "passive"))
    )
    (net (code "221") (name "unconnected-(IC5-PG6-Pad91)") (class "Default")
      (node (ref "IC5") (pin "91") (pinfunction "PG6_91") (pintype "passive"))
    )
    (net (code "222") (name "unconnected-(IC5-PG7-Pad92)") (class "Default")
      (node (ref "IC5") (pin "92") (pinfunction "PG7_92") (pintype "passive"))
    )
    (net (code "223") (name "unconnected-(IC5-PG8-Pad93)") (class "Default")
      (node (ref "IC5") (pin "93") (pinfunction "PG8_93") (pintype "passive"))
    )
    (net (code "224") (name "unconnected-(IC5-PG9-Pad124)") (class "Default")
      (node (ref "IC5") (pin "124") (pinfunction "PG9_124") (pintype "passive"))
    )
    (net (code "225") (name "unconnected-(IC5-PG10-Pad125)") (class "Default")
      (node (ref "IC5") (pin "125") (pinfunction "PG10_125") (pintype "passive"))
    )
    (net (code "226") (name "unconnected-(IC5-PG14-Pad129)") (class "Default")
      (node (ref "IC5") (pin "129") (pinfunction "PG14_129") (pintype "passive"))
    )
    (net (code "227") (name "unconnected-(IC5-PG15-Pad132)") (class "Default")
      (node (ref "IC5") (pin "132") (pinfunction "PG15_132") (pintype "passive"))
    )
    (net (code "228") (name "unconnected-(IC5-PH0-OSC_IN-Pad23)") (class "Default")
      (node (ref "IC5") (pin "23") (pinfunction "PH0-OSC_IN_23") (pintype "passive"))
    )
    (net (code "229") (name "unconnected-(IC5-PH1-OSC_OUT-Pad24)") (class "Default")
      (node (ref "IC5") (pin "24") (pinfunction "PH1-OSC_OUT_24") (pintype "passive"))
    )
    (net (code "230") (name "unconnected-(IC5-VBAT-Pad6)") (class "Default")
      (node (ref "IC5") (pin "6") (pinfunction "VBAT_6") (pintype "passive"))
    )
    (net (code "231") (name "unconnected-(IC5-VSS_6-Pad94)") (class "Default")
      (node (ref "IC5") (pin "94") (pinfunction "VSS_6_94") (pintype "passive"))
    )
    (net (code "232") (name "unconnected-(IC5-VSS_9-Pad130)") (class "Default")
      (node (ref "IC5") (pin "130") (pinfunction "VSS_9_130") (pintype "passive"))
    )
    (net (code "233") (name "unconnected-(JALT-Pad3)") (class "Default")
      (node (ref "JALT") (pin "3") (pinfunction "3_3") (pintype "passive+no_connect"))
    )
    (net (code "234") (name "unconnected-(JALT-Pad6)") (class "Default")
      (node (ref "JALT") (pin "6") (pinfunction "6_6") (pintype "passive+no_connect"))
    )
    (net (code "235") (name "unconnected-(JALT-Pad7)") (class "Default")
      (node (ref "JALT") (pin "7") (pinfunction "7_7") (pintype "passive+no_connect"))
    )
    (net (code "236") (name "unconnected-(JIMU-3VO-Pad2)") (class "Default")
      (node (ref "JIMU") (pin "2") (pinfunction "3VO_2") (pintype "passive+no_connect"))
    )
    (net (code "237") (name "unconnected-(JIMU-ADR-Pad10)") (class "Default")
      (node (ref "JIMU") (pin "10") (pinfunction "ADR_10") (pintype "passive+no_connect"))
    )
    (net (code "238") (name "unconnected-(JIMU-PS0-Pad7)") (class "Default")
      (node (ref "JIMU") (pin "7") (pinfunction "PS0_7") (pintype "passive+no_connect"))
    )
    (net (code "239") (name "unconnected-(JIMU-PS1-Pad8)") (class "Default")
      (node (ref "JIMU") (pin "8") (pinfunction "PS1_8") (pintype "passive+no_connect"))
    )
    (net (code "240") (name "unconnected-(JIMU-PadMH1)") (class "Default")
      (node (ref "JIMU") (pin "MH1") (pinfunction "MH1_MH1") (pintype "passive+no_connect"))
    )
    (net (code "241") (name "unconnected-(JIMU-PadMH2)") (class "Default")
      (node (ref "JIMU") (pin "MH2") (pinfunction "MH2_MH2") (pintype "passive+no_connect"))
    )
    (net (code "242") (name "unconnected-(JIMU-PadMH3)") (class "Default")
      (node (ref "JIMU") (pin "MH3") (pinfunction "MH3_MH3") (pintype "passive+no_connect"))
    )
    (net (code "243") (name "unconnected-(JIMU-PadMH4)") (class "Default")
      (node (ref "JIMU") (pin "MH4") (pinfunction "MH4_MH4") (pintype "passive+no_connect"))
    )
    (net (code "244") (name "unconnected-(U4-3VO-Pad2)") (class "Default")
      (node (ref "U4") (pin "2") (pinfunction "3VO_2") (pintype "power_in+no_connect"))
    )
    (net (code "245") (name "unconnected-(U4-SDO{slash}ADR-Pad5)") (class "Default")
      (node (ref "U4") (pin "5") (pinfunction "SDO/ADR_5") (pintype "bidirectional+no_connect"))
    )
  )
)
